# LJU_SNAP.net
KiCad netlist of a schematic drawn in Altium Designer
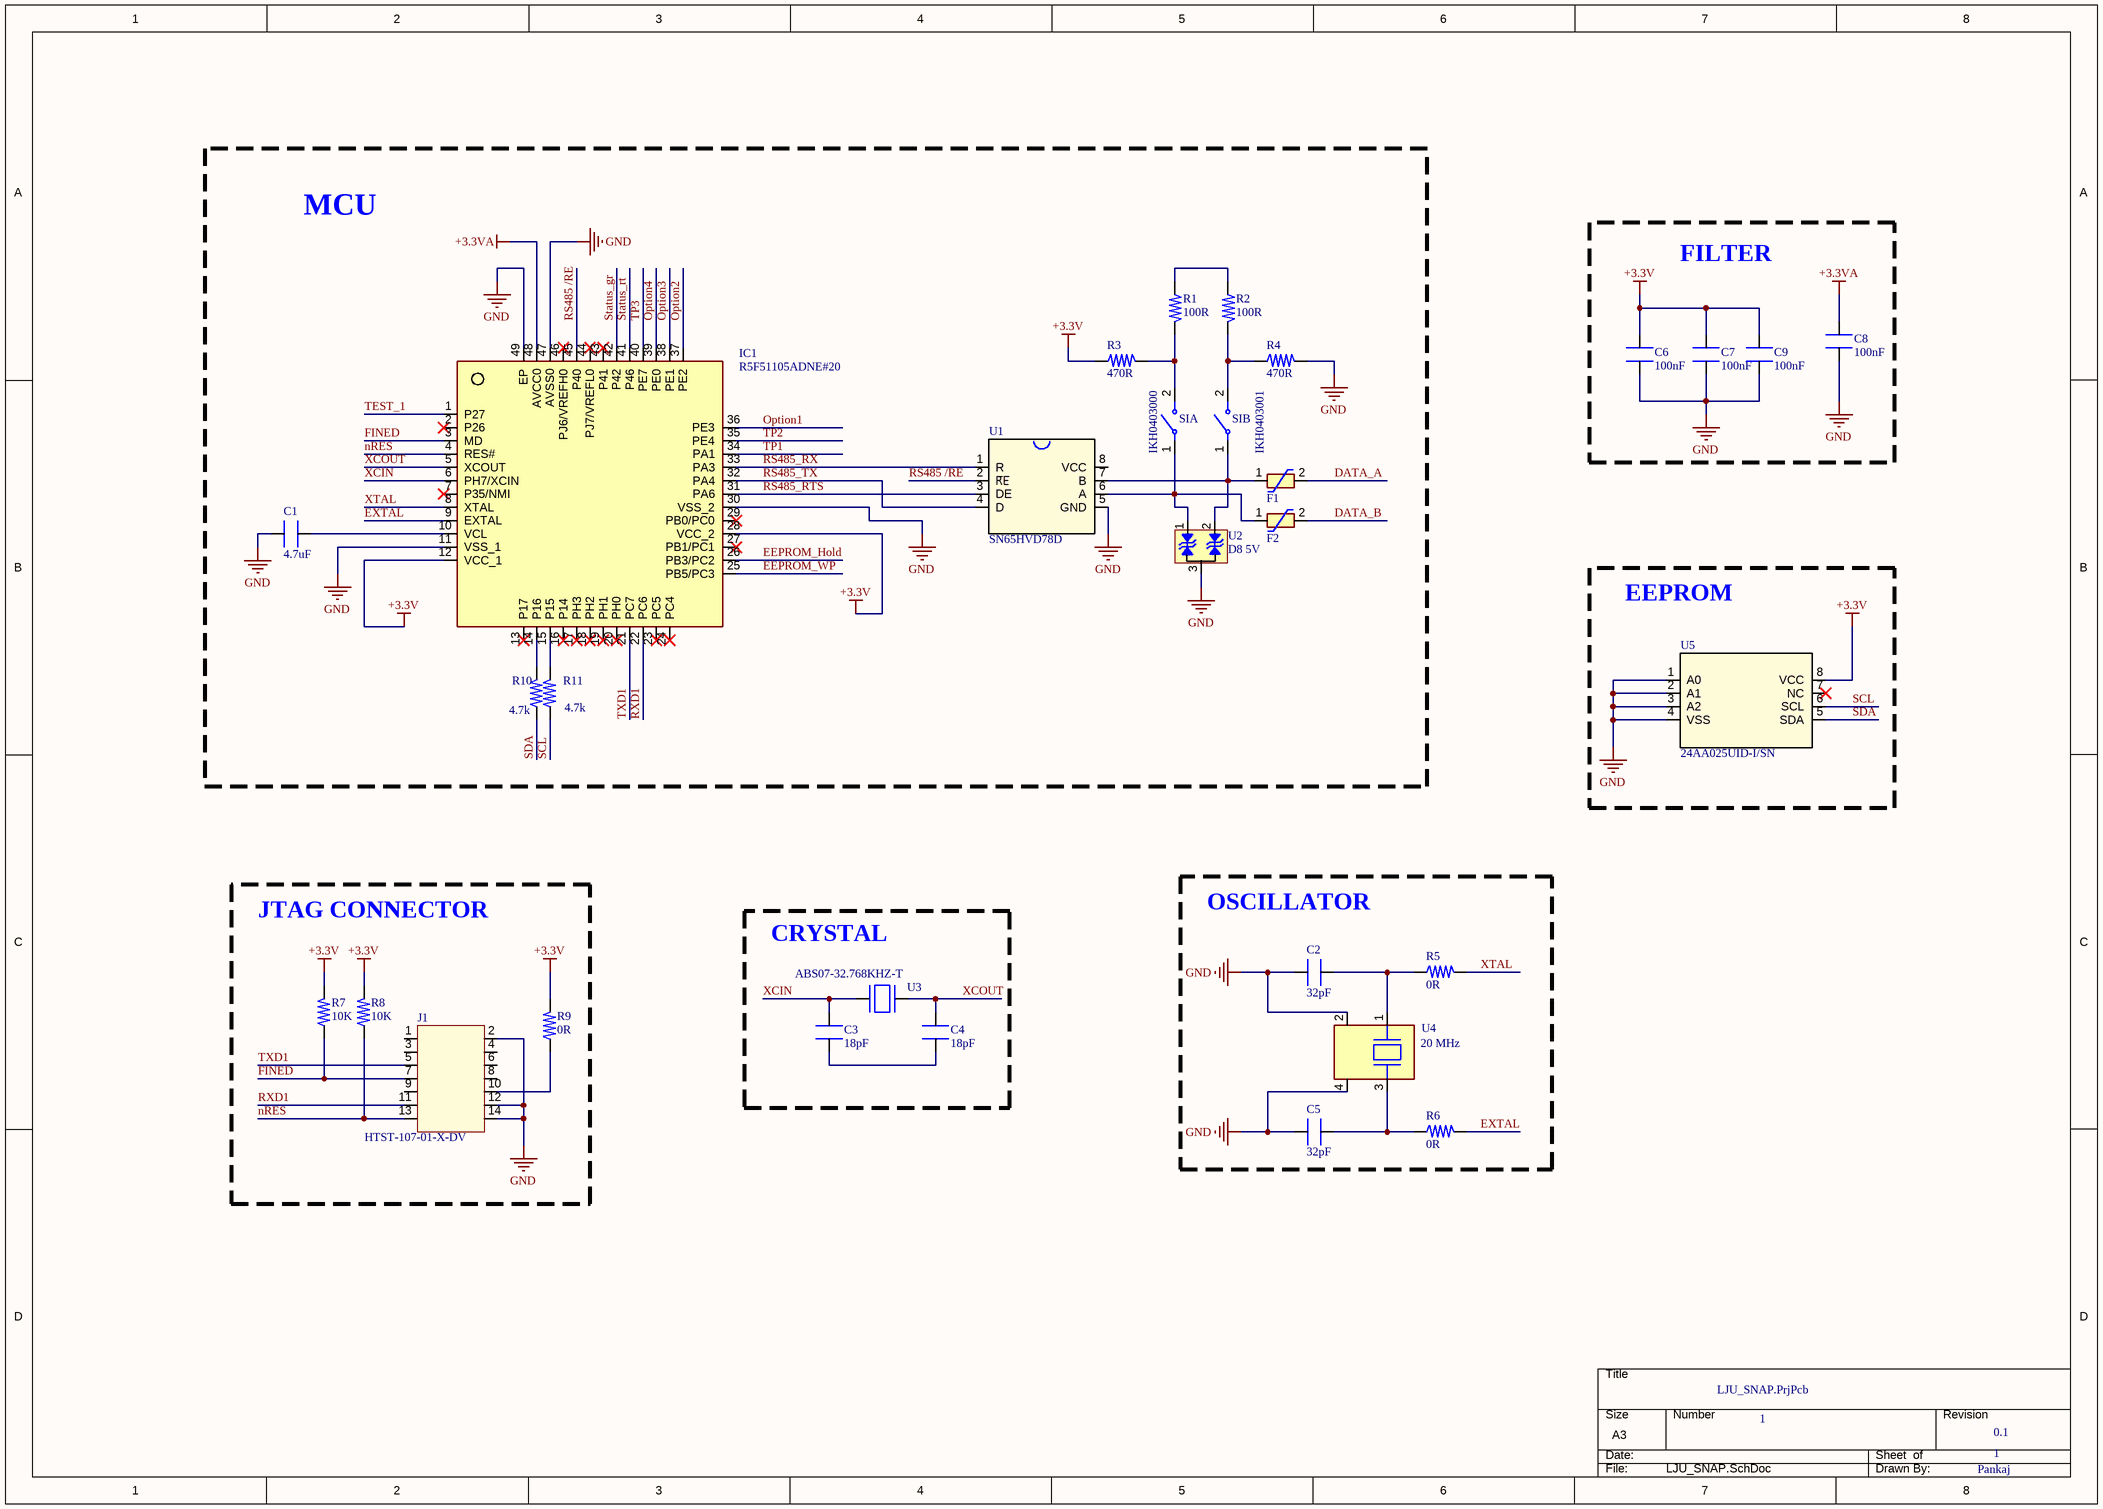
[diagram p0: LJU_SNAP.SchDoc]

(export (version "E")
  (design (tool "Eeschema 10.0.6"))
  (components
    (comp (ref "C1")
      (value "4.7uF")
      (footprint "CAP")
      (description "4.7 µF ±10% 25V Ceramic Capacitor X5R 0603 (1608 Metric)")
      (fields
        (field (name "MANUFACTURER") "KEMET")
        (field (name "MANUFACTURING PART NUMBER") "C0603C104K5RACTU")
      )
      (libsource (lib "SCH_LIB") (part "GRM188R61E475KE11D"))
    )
    (comp (ref "C2")
      (value "32pF")
      (footprint "CAP")
      (description "32 pF ±1% 50V Ceramic Capacitor C0G, NP0 0603 (1608 Metric)")
      (fields
        (field (name "MANUFACTURER") "KEMET")
        (field (name "MANUFACTURING PART NUMBER") "C0603C104K5RACTU")
      )
      (libsource (lib "SCH_LIB") (part "06035A320FAT4A"))
    )
    (comp (ref "C3")
      (value "18pF")
      (footprint "CAP")
      (description "CAP THIN FILM 21PF 25V 0402")
      (fields
        (field (name "MANUFACTURER") "KEMET")
        (field (name "MANUFACTURING PART NUMBER") "C0603C104K5RACTU")
      )
      (libsource (lib "SCH_LIB") (part "04023K210FBWTR{backslash}500"))
    )
    (comp (ref "C4")
      (value "18pF")
      (footprint "CAP")
      (description "CAP THIN FILM 21PF 25V 0402")
      (fields
        (field (name "MANUFACTURER") "KEMET")
        (field (name "MANUFACTURING PART NUMBER") "C0603C104K5RACTU")
      )
      (libsource (lib "SCH_LIB") (part "04023K210FBWTR{backslash}500"))
    )
    (comp (ref "C5")
      (value "32pF")
      (footprint "CAP")
      (description "32 pF ±1% 50V Ceramic Capacitor C0G, NP0 0603 (1608 Metric)")
      (fields
        (field (name "MANUFACTURER") "KEMET")
        (field (name "MANUFACTURING PART NUMBER") "C0603C104K5RACTU")
      )
      (libsource (lib "SCH_LIB") (part "06035A320FAT4A"))
    )
    (comp (ref "C6")
      (value "100nF")
      (footprint "CAP")
      (description "100 nF ±10% 100V Ceramic Capacitor X8L 0603 (1608 Metric)")
      (fields
        (field (name "MANUFACTURER") "KEMET")
        (field (name "MANUFACTURING PART NUMBER") "C0603C104K5RACTU")
      )
      (libsource (lib "SCH_LIB") (part "CL10E104KC8VPNC"))
    )
    (comp (ref "C7")
      (value "100nF")
      (footprint "CAP")
      (description "100 nF ±10% 100V Ceramic Capacitor X8L 0603 (1608 Metric)")
      (fields
        (field (name "MANUFACTURER") "KEMET")
        (field (name "MANUFACTURING PART NUMBER") "C0603C104K5RACTU")
      )
      (libsource (lib "SCH_LIB") (part "CL10E104KC8VPNC"))
    )
    (comp (ref "C8")
      (value "100nF")
      (footprint "CAP")
      (description "100 nF ±10% 100V Ceramic Capacitor X8L 0603 (1608 Metric)")
      (fields
        (field (name "MANUFACTURER") "KEMET")
        (field (name "MANUFACTURING PART NUMBER") "C0603C104K5RACTU")
      )
      (libsource (lib "SCH_LIB") (part "CL10E104KC8VPNC"))
    )
    (comp (ref "C9")
      (value "100nF")
      (footprint "CAP")
      (description "100 nF ±10% 100V Ceramic Capacitor X8L 0603 (1608 Metric)")
      (fields
        (field (name "MANUFACTURER") "KEMET")
        (field (name "MANUFACTURING PART NUMBER") "C0603C104K5RACTU")
      )
      (libsource (lib "SCH_LIB") (part "CL10E104KC8VPNC"))
    )
    (comp (ref "F1")
      (value "FUSE")
      (footprint "RESC3216X125N")
      (description "Polymeric PTC Resettable Fuse 24V 200 mA Ih Surface Mount 1206 (3216 Metric), Concave")
      (fields (field (name "MF") "Panasonic") (field (name "MP") "ERB-RE5R00V"))
      (libsource (lib "SCH_LIB") (part "PTS120624V020"))
    )
    (comp (ref "F2")
      (value "FUSE")
      (footprint "RESC3216X125N")
      (description "Polymeric PTC Resettable Fuse 24V 200 mA Ih Surface Mount 1206 (3216 Metric), Concave")
      (fields (field (name "MF") "Panasonic") (field (name "MP") "ERB-RE5R00V"))
      (libsource (lib "SCH_LIB") (part "PTS120624V020"))
    )
    (comp (ref "IC1")
      (value "R5F51105ADNE#20")
      (footprint "PCB_LIB:QFN50P700X700X80-49N-D")
      (description "Integrated Circuit")
      (libsource (lib "SCH_LIB") (part "R5F51105ADNE#20"))
    )
    (comp (ref "IKH1")
      (value "SIA")
      (footprint "SW_DS01-254-L-01BE")
      (libsource (lib "SCH_LIB") (part "IKH0403000"))
    )
    (comp (ref "IKH2")
      (value "SIB")
      (footprint "SW_DS01-254-L-01BE")
      (libsource (lib "SCH_LIB") (part "IKH0403000"))
    )
    (comp (ref "J1")
      (value "HTST-107-01-X-DV")
      (footprint "SAMTEC-HTST-107-01-X-DV")
      (fields (field (name "MP") "SAMTEC-HTST-107-01-X-DV"))
      (libsource (lib "SCH_LIB") (part "SAMTEC-HTST-107-01-X-DV"))
    )
    (comp (ref "R1")
      (value "100R")
      (footprint "RES")
      (description "100 Ohms ±1% 0.1W, 1/10W Chip Resistor 0603 (1608 Metric) Moisture Resistant Thick Film")
      (fields
        (field (name "MANUFACTURER") "Vishay Dale")
        (field (name "MANUFACTURER PART NUMBER") "CRCW0603590KFKEA")
      )
      (libsource (lib "SCH_LIB") (part "RC0603FR-07100RL"))
    )
    (comp (ref "R2")
      (value "100R")
      (footprint "RES")
      (description "100 Ohms ±1% 0.1W, 1/10W Chip Resistor 0603 (1608 Metric) Moisture Resistant Thick Film")
      (fields
        (field (name "MANUFACTURER") "Vishay Dale")
        (field (name "MANUFACTURER PART NUMBER") "CRCW0603590KFKEA")
      )
      (libsource (lib "SCH_LIB") (part "RC0603FR-07100RL"))
    )
    (comp (ref "R3")
      (value "470R")
      (footprint "RES")
      (description "470 Ohms ±5% 0.1W, 1/10W Chip Resistor 0603 (1608 Metric) Moisture Resistant Thick Film")
      (fields
        (field (name "MANUFACTURER") "Vishay Dale")
        (field (name "MANUFACTURER PART NUMBER") "CRCW0603590KFKEA")
      )
      (libsource (lib "SCH_LIB") (part "RC0603JR-07470RL"))
    )
    (comp (ref "R4")
      (value "470R")
      (footprint "RES")
      (description "470 Ohms ±5% 0.1W, 1/10W Chip Resistor 0603 (1608 Metric) Moisture Resistant Thick Film")
      (fields
        (field (name "MANUFACTURER") "Vishay Dale")
        (field (name "MANUFACTURER PART NUMBER") "CRCW0603590KFKEA")
      )
      (libsource (lib "SCH_LIB") (part "RC0603JR-07470RL"))
    )
    (comp (ref "R5")
      (value "0R")
      (footprint "RES")
      (description "0 Ohms Jumper 0.1W, 1/10W Chip Resistor 0603 (1608 Metric) Thick Film")
      (fields
        (field (name "MANUFACTURER") "YAGEO")
        (field (name "MANUFACTURER PART NUMBER") "RC0603FR-0710KL")
      )
      (libsource (lib "SCH_LIB") (part "CR0603PB0RS001"))
    )
    (comp (ref "R6")
      (value "0R")
      (footprint "RES")
      (description "0 Ohms Jumper 0.1W, 1/10W Chip Resistor 0603 (1608 Metric) Thick Film")
      (fields
        (field (name "MANUFACTURER") "YAGEO")
        (field (name "MANUFACTURER PART NUMBER") "RC0603FR-0710KL")
      )
      (libsource (lib "SCH_LIB") (part "CR0603PB0RS001"))
    )
    (comp (ref "R7")
      (value "10K")
      (footprint "RES")
      (description "10 kOhms ±1% 0.1W, 1/10W Chip Resistor 0603 (1608 Metric) Moisture Resistant Thick Film")
      (fields
        (field (name "MANUFACTURER") "YAGEO")
        (field (name "MANUFACTURER PART NUMBER") "RC0603FR-0710KL")
      )
      (libsource (lib "SCH_LIB") (part "RC0603FR-0710KL"))
    )
    (comp (ref "R8")
      (value "10K")
      (footprint "RES")
      (description "10 kOhms ±1% 0.1W, 1/10W Chip Resistor 0603 (1608 Metric) Moisture Resistant Thick Film")
      (fields
        (field (name "MANUFACTURER") "YAGEO")
        (field (name "MANUFACTURER PART NUMBER") "RC0603FR-0710KL")
      )
      (libsource (lib "SCH_LIB") (part "RC0603FR-0710KL"))
    )
    (comp (ref "R9")
      (value "0R")
      (footprint "RES")
      (description "0 Ohms Jumper 0.1W, 1/10W Chip Resistor 0603 (1608 Metric) Thick Film")
      (fields
        (field (name "MANUFACTURER") "YAGEO")
        (field (name "MANUFACTURER PART NUMBER") "RC0603FR-0710KL")
      )
      (libsource (lib "SCH_LIB") (part "CR0603PB0RS001"))
    )
    (comp (ref "R10")
      (value "4.7k")
      (footprint "RES")
      (description "4.7 kOhms ±1% 0.1W, 1/10W Chip Resistor 0603 (1608 Metric) Moisture Resistant Thick Film")
      (fields
        (field (name "MANUFACTURER") "YAGEO")
        (field (name "MANUFACTURER PART NUMBER") "RC0603FR-0710KL")
      )
      (libsource (lib "SCH_LIB") (part "RC0603FR-074K7L"))
    )
    (comp (ref "R11")
      (value "4.7k")
      (footprint "RES")
      (description "4.7 kOhms ±1% 0.1W, 1/10W Chip Resistor 0603 (1608 Metric) Moisture Resistant Thick Film")
      (fields
        (field (name "MANUFACTURER") "YAGEO")
        (field (name "MANUFACTURER PART NUMBER") "RC0603FR-0710KL")
      )
      (libsource (lib "SCH_LIB") (part "RC0603FR-074K7L"))
    )
    (comp (ref "U1")
      (value "SN65HVD78D")
      (footprint "D8_TEX")
      (description "3.3 V Half-Duplex RS-485, with IEC ESD, 50 Mbps 8-SOIC -40 to 125")
      (fields (field (name "COPYRIGHT") "Copyright (C) 2025 Ultra Librarian. All rights reserved."))
      (libsource (lib "SCH_LIB") (part "SN65HVD78D"))
    )
    (comp (ref "U2")
      (value "D8 5V")
      (footprint "SOT-23-3_DBZ_TEX")
      (description "Two-channel bidirectional 12V ESD protection diode 3-SOT-23 -40 to 125")
      (libsource (lib "SCH_LIB") (part "ESD562DBZR"))
    )
    (comp (ref "U3")
      (value "ABS07-32.768KHZ-T")
      (footprint "XTAL_ABS07-32.768KHZ-T")
      (description "32.768 kHz Â±20ppm Crystal 12.5pF 70 kOhms 2-SMD, No Lead")
      (fields (field (name "MF") "Abracon"))
      (libsource (lib "SCH_LIB") (part "ABS07-32.768KHZ-T"))
    )
    (comp (ref "U4")
      (value "20 MHz")
      (footprint "XTAL_ABM8AIG-20.000MHZ-12-2Z-T3")
      (description "20 MHz Â±20ppm Crystal 12pF 50 Ohms 4-SMD, No Lead")
      (fields (field (name "MP") "ABM8AIG-20.000MHZ-12-2Z-T3") (field (name "MF") "Abracon"))
      (libsource (lib "SCH_LIB") (part "ABM8AIG-20.000MHZ-12-2Z-T3"))
    )
    (comp (ref "U5")
      (value "24AA025UID-I/SN")
      (footprint "SOIC8-N_MC_MCH")
      (description "EEPROM Memory IC 2Kbit I2C 400 kHz 900 ns 8-SOIC")
      (fields (field (name "COPYRIGHT") "Copyright (C) 2025 Ultra Librarian. All rights reserved."))
      (libsource (lib "SCH_LIB") (part "24AA025UID-ISN"))
    )
  )
  (nets
    (net (code "1") (name "+3.3V") (class "Default")
      (node (ref "C6") (pin "2") (pinfunction "2_2") (pintype "passive"))
      (node (ref "C7") (pin "2") (pinfunction "2_2") (pintype "passive"))
      (node (ref "C9") (pin "2") (pinfunction "2_2") (pintype "passive"))
      (node (ref "IC1") (pin "12") (pinfunction "VCC_1_12") (pintype "passive"))
      (node (ref "IC1") (pin "28") (pinfunction "VCC_2_28") (pintype "passive"))
      (node (ref "R3") (pin "1") (pinfunction "1_1") (pintype "passive"))
      (node (ref "R7") (pin "2") (pinfunction "2_2") (pintype "passive"))
      (node (ref "R8") (pin "2") (pinfunction "2_2") (pintype "passive"))
      (node (ref "R9") (pin "2") (pinfunction "2_2") (pintype "passive"))
      (node (ref "U5") (pin "8") (pinfunction "VCC_8") (pintype "passive"))
    )
    (net (code "2") (name "+3.3VA") (class "Default")
      (node (ref "C8") (pin "2") (pinfunction "2_2") (pintype "passive"))
      (node (ref "IC1") (pin "48") (pinfunction "AVCC0_48") (pintype "passive"))
    )
    (net (code "3") (name "/DATA_A") (class "Default")
      (node (ref "F1") (pin "2") (pinfunction "2_2") (pintype "passive"))
    )
    (net (code "4") (name "/DATA_B") (class "Default")
      (node (ref "F2") (pin "2") (pinfunction "2_2") (pintype "passive"))
    )
    (net (code "5") (name "/EEPROM_Hold") (class "Default")
      (node (ref "IC1") (pin "26") (pinfunction "PB3/PC2_26") (pintype "passive"))
    )
    (net (code "6") (name "/EEPROM_WP") (class "Default")
      (node (ref "IC1") (pin "25") (pinfunction "PB5/PC3_25") (pintype "passive"))
    )
    (net (code "7") (name "/EXTAL") (class "Default")
      (node (ref "IC1") (pin "9") (pinfunction "EXTAL_9") (pintype "passive"))
      (node (ref "R6") (pin "2") (pinfunction "2_2") (pintype "passive"))
    )
    (net (code "8") (name "/FINED") (class "Default")
      (node (ref "IC1") (pin "3") (pinfunction "MD_3") (pintype "passive"))
      (node (ref "J1") (pin "7") (pinfunction "7_7") (pintype "passive"))
      (node (ref "R7") (pin "1") (pinfunction "1_1") (pintype "passive"))
    )
    (net (code "9") (name "/Option1") (class "Default")
      (node (ref "IC1") (pin "36") (pinfunction "PE3_36") (pintype "passive"))
    )
    (net (code "10") (name "/Option2") (class "Default")
      (node (ref "IC1") (pin "37") (pinfunction "PE2_37") (pintype "passive"))
    )
    (net (code "11") (name "/Option3") (class "Default")
      (node (ref "IC1") (pin "38") (pinfunction "PE1_38") (pintype "passive"))
    )
    (net (code "12") (name "/Option4") (class "Default")
      (node (ref "IC1") (pin "39") (pinfunction "PE0_39") (pintype "passive"))
    )
    (net (code "13") (name "/RS485 {slash}RE") (class "Default")
      (node (ref "IC1") (pin "45") (pinfunction "P40_45") (pintype "passive"))
      (node (ref "U1") (pin "2") (pinfunction "R̅E̅_2") (pintype "passive"))
    )
    (net (code "14") (name "/RS485_RTS") (class "Default")
      (node (ref "IC1") (pin "31") (pinfunction "PA6_31") (pintype "passive"))
      (node (ref "U1") (pin "3") (pinfunction "DE_3") (pintype "passive"))
    )
    (net (code "15") (name "/RS485_RX") (class "Default")
      (node (ref "IC1") (pin "33") (pinfunction "PA3_33") (pintype "passive"))
      (node (ref "U1") (pin "1") (pinfunction "R_1") (pintype "passive"))
    )
    (net (code "16") (name "/RS485_TX") (class "Default")
      (node (ref "IC1") (pin "32") (pinfunction "PA4_32") (pintype "passive"))
      (node (ref "U1") (pin "4") (pinfunction "D_4") (pintype "passive"))
    )
    (net (code "17") (name "/RXD1") (class "Default")
      (node (ref "IC1") (pin "22") (pinfunction "PC6_22") (pintype "passive"))
      (node (ref "J1") (pin "11") (pinfunction "11_11") (pintype "passive"))
    )
    (net (code "18") (name "/SCL") (class "Default")
      (node (ref "R11") (pin "1") (pinfunction "1_1") (pintype "passive"))
      (node (ref "U5") (pin "6") (pinfunction "SCL_6") (pintype "passive"))
    )
    (net (code "19") (name "/SDA") (class "Default")
      (node (ref "R10") (pin "1") (pinfunction "1_1") (pintype "passive"))
      (node (ref "U5") (pin "5") (pinfunction "SDA_5") (pintype "passive"))
    )
    (net (code "20") (name "/Status_gr") (class "Default")
      (node (ref "IC1") (pin "42") (pinfunction "P42_42") (pintype "passive"))
    )
    (net (code "21") (name "/Status_rt") (class "Default")
      (node (ref "IC1") (pin "41") (pinfunction "P46_41") (pintype "passive"))
    )
    (net (code "22") (name "/TEST_1") (class "Default")
      (node (ref "IC1") (pin "1") (pinfunction "P27_1") (pintype "passive"))
    )
    (net (code "23") (name "/TP1") (class "Default")
      (node (ref "IC1") (pin "34") (pinfunction "PA1_34") (pintype "passive"))
    )
    (net (code "24") (name "/TP2") (class "Default")
      (node (ref "IC1") (pin "35") (pinfunction "PE4_35") (pintype "passive"))
    )
    (net (code "25") (name "/TP3") (class "Default")
      (node (ref "IC1") (pin "40") (pinfunction "PE7_40") (pintype "passive"))
    )
    (net (code "26") (name "/TXD1") (class "Default")
      (node (ref "IC1") (pin "21") (pinfunction "PC7_21") (pintype "passive"))
      (node (ref "J1") (pin "5") (pinfunction "5_5") (pintype "passive"))
    )
    (net (code "27") (name "/XCIN") (class "Default")
      (node (ref "C3") (pin "2") (pinfunction "2_2") (pintype "passive"))
      (node (ref "IC1") (pin "6") (pinfunction "PH7/XCIN_6") (pintype "passive"))
      (node (ref "U3") (pin "1") (pinfunction "1_1") (pintype "passive"))
    )
    (net (code "28") (name "/XCOUT") (class "Default")
      (node (ref "C4") (pin "2") (pinfunction "2_2") (pintype "passive"))
      (node (ref "IC1") (pin "5") (pinfunction "XCOUT_5") (pintype "passive"))
      (node (ref "U3") (pin "2") (pinfunction "2_2") (pintype "passive"))
    )
    (net (code "29") (name "/XTAL") (class "Default")
      (node (ref "IC1") (pin "8") (pinfunction "XTAL_8") (pintype "passive"))
      (node (ref "R5") (pin "2") (pinfunction "2_2") (pintype "passive"))
    )
    (net (code "30") (name "/nRES") (class "Default")
      (node (ref "IC1") (pin "4") (pinfunction "RES#_4") (pintype "passive"))
      (node (ref "J1") (pin "13") (pinfunction "13_13") (pintype "passive"))
      (node (ref "R8") (pin "1") (pinfunction "1_1") (pintype "passive"))
    )
    (net (code "31") (name "GND") (class "Default")
      (node (ref "C1") (pin "1") (pinfunction "1_1") (pintype "passive"))
      (node (ref "C2") (pin "1") (pinfunction "1_1") (pintype "passive"))
      (node (ref "C5") (pin "1") (pinfunction "1_1") (pintype "passive"))
      (node (ref "C6") (pin "1") (pinfunction "1_1") (pintype "passive"))
      (node (ref "C7") (pin "1") (pinfunction "1_1") (pintype "passive"))
      (node (ref "C8") (pin "1") (pinfunction "1_1") (pintype "passive"))
      (node (ref "C9") (pin "1") (pinfunction "1_1") (pintype "passive"))
      (node (ref "IC1") (pin "11") (pinfunction "VSS_1_11") (pintype "passive"))
      (node (ref "IC1") (pin "30") (pinfunction "VSS_2_30") (pintype "passive"))
      (node (ref "IC1") (pin "47") (pinfunction "AVSS0_47") (pintype "passive"))
      (node (ref "IC1") (pin "49") (pinfunction "EP_49") (pintype "passive"))
      (node (ref "J1") (pin "12") (pinfunction "12_12") (pintype "passive"))
      (node (ref "J1") (pin "14") (pinfunction "14_14") (pintype "passive"))
      (node (ref "J1") (pin "2") (pinfunction "2_2") (pintype "passive"))
      (node (ref "R4") (pin "2") (pinfunction "2_2") (pintype "passive"))
      (node (ref "U1") (pin "5") (pinfunction "GND_5") (pintype "power_in"))
      (node (ref "U2") (pin "3") (pinfunction "3_3") (pintype "passive"))
      (node (ref "U4") (pin "2") (pinfunction "GND_2") (pintype "power_in"))
      (node (ref "U4") (pin "4") (pinfunction "GND_4") (pintype "power_in"))
      (node (ref "U5") (pin "1") (pinfunction "A0_1") (pintype "passive"))
      (node (ref "U5") (pin "2") (pinfunction "A1_2") (pintype "passive"))
      (node (ref "U5") (pin "3") (pinfunction "A2_3") (pintype "passive"))
      (node (ref "U5") (pin "4") (pinfunction "VSS_4") (pintype "passive"))
    )
    (net (code "32") (name "Net-(C2-Pad2)") (class "Default")
      (node (ref "C2") (pin "2") (pinfunction "2_2") (pintype "passive"))
      (node (ref "R5") (pin "1") (pinfunction "1_1") (pintype "passive"))
      (node (ref "U4") (pin "1") (pinfunction "1_1") (pintype "passive"))
    )
    (net (code "33") (name "Net-(C3-Pad1)") (class "Default")
      (node (ref "C3") (pin "1") (pinfunction "1_1") (pintype "passive"))
      (node (ref "C4") (pin "1") (pinfunction "1_1") (pintype "passive"))
    )
    (net (code "34") (name "Net-(IC1-P15)") (class "Default")
      (node (ref "IC1") (pin "15") (pinfunction "P15_15") (pintype "passive"))
      (node (ref "R11") (pin "2") (pinfunction "2_2") (pintype "passive"))
    )
    (net (code "35") (name "Net-(IC1-P16)") (class "Default")
      (node (ref "IC1") (pin "14") (pinfunction "P16_14") (pintype "passive"))
      (node (ref "R10") (pin "2") (pinfunction "2_2") (pintype "passive"))
    )
    (net (code "36") (name "Net-(IC1-VCL)") (class "Default")
      (node (ref "C1") (pin "2") (pinfunction "2_2") (pintype "passive"))
      (node (ref "IC1") (pin "10") (pinfunction "VCL_10") (pintype "passive"))
    )
    (net (code "37") (name "Net-(IKH1-Pad2)") (class "Default")
      (node (ref "IKH1") (pin "2") (pinfunction "2_2") (pintype "passive"))
      (node (ref "R1") (pin "2") (pinfunction "2_2") (pintype "passive"))
      (node (ref "R3") (pin "2") (pinfunction "2_2") (pintype "passive"))
    )
    (net (code "38") (name "Net-(IKH2-Pad2)") (class "Default")
      (node (ref "IKH2") (pin "2") (pinfunction "2_2") (pintype "passive"))
      (node (ref "R2") (pin "2") (pinfunction "2_2") (pintype "passive"))
      (node (ref "R4") (pin "1") (pinfunction "1_1") (pintype "passive"))
    )
    (net (code "39") (name "Net-(J1-Pad10)") (class "Default")
      (node (ref "J1") (pin "10") (pinfunction "10_10") (pintype "passive"))
      (node (ref "R9") (pin "1") (pinfunction "1_1") (pintype "passive"))
    )
    (net (code "40") (name "Net-(R1-Pad1)") (class "Default")
      (node (ref "R1") (pin "1") (pinfunction "1_1") (pintype "passive"))
      (node (ref "R2") (pin "1") (pinfunction "1_1") (pintype "passive"))
    )
    (net (code "41") (name "Net-(U1-A)") (class "Default")
      (node (ref "F2") (pin "1") (pinfunction "1_1") (pintype "passive"))
      (node (ref "IKH1") (pin "1") (pinfunction "1_1") (pintype "passive"))
      (node (ref "U1") (pin "6") (pinfunction "A_6") (pintype "passive"))
      (node (ref "U2") (pin "1") (pintype "passive"))
    )
    (net (code "42") (name "Net-(U1-B)") (class "Default")
      (node (ref "F1") (pin "1") (pinfunction "1_1") (pintype "passive"))
      (node (ref "IKH2") (pin "1") (pinfunction "1_1") (pintype "passive"))
      (node (ref "U1") (pin "7") (pinfunction "B_7") (pintype "passive"))
      (node (ref "U2") (pin "2") (pintype "passive"))
    )
    (net (code "43") (name "Net-(U4-2)") (class "Default")
      (node (ref "C5") (pin "2") (pinfunction "2_2") (pintype "passive"))
      (node (ref "R6") (pin "1") (pinfunction "1_1") (pintype "passive"))
      (node (ref "U4") (pin "3") (pinfunction "2_3") (pintype "passive"))
    )
    (net (code "44") (name "unconnected-(IC1-P14-Pad16)") (class "Default")
      (node (ref "IC1") (pin "16") (pinfunction "P14_16") (pintype "passive+no_connect"))
    )
    (net (code "45") (name "unconnected-(IC1-P17-Pad13)") (class "Default")
      (node (ref "IC1") (pin "13") (pinfunction "P17_13") (pintype "passive+no_connect"))
    )
    (net (code "46") (name "unconnected-(IC1-P26-Pad2)") (class "Default")
      (node (ref "IC1") (pin "2") (pinfunction "P26_2") (pintype "passive+no_connect"))
    )
    (net (code "47") (name "unconnected-(IC1-P35{slash}NMI-Pad7)") (class "Default")
      (node (ref "IC1") (pin "7") (pinfunction "P35/NMI_7") (pintype "passive+no_connect"))
    )
    (net (code "48") (name "unconnected-(IC1-P41-Pad43)") (class "Default")
      (node (ref "IC1") (pin "43") (pinfunction "P41_43") (pintype "passive+no_connect"))
    )
    (net (code "49") (name "unconnected-(IC1-PB0{slash}PC0-Pad29)") (class "Default")
      (node (ref "IC1") (pin "29") (pinfunction "PB0/PC0_29") (pintype "passive+no_connect"))
    )
    (net (code "50") (name "unconnected-(IC1-PB1{slash}PC1-Pad27)") (class "Default")
      (node (ref "IC1") (pin "27") (pinfunction "PB1/PC1_27") (pintype "passive+no_connect"))
    )
    (net (code "51") (name "unconnected-(IC1-PC4-Pad24)") (class "Default")
      (node (ref "IC1") (pin "24") (pinfunction "PC4_24") (pintype "passive+no_connect"))
    )
    (net (code "52") (name "unconnected-(IC1-PC5-Pad23)") (class "Default")
      (node (ref "IC1") (pin "23") (pinfunction "PC5_23") (pintype "passive+no_connect"))
    )
    (net (code "53") (name "unconnected-(IC1-PH0-Pad20)") (class "Default")
      (node (ref "IC1") (pin "20") (pinfunction "PH0_20") (pintype "passive+no_connect"))
    )
    (net (code "54") (name "unconnected-(IC1-PH1-Pad19)") (class "Default")
      (node (ref "IC1") (pin "19") (pinfunction "PH1_19") (pintype "passive+no_connect"))
    )
    (net (code "55") (name "unconnected-(IC1-PH2-Pad18)") (class "Default")
      (node (ref "IC1") (pin "18") (pinfunction "PH2_18") (pintype "passive+no_connect"))
    )
    (net (code "56") (name "unconnected-(IC1-PH3-Pad17)") (class "Default")
      (node (ref "IC1") (pin "17") (pinfunction "PH3_17") (pintype "passive+no_connect"))
    )
    (net (code "57") (name "unconnected-(IC1-PJ6{slash}VREFH0-Pad46)") (class "Default")
      (node (ref "IC1") (pin "46") (pinfunction "PJ6/VREFH0_46") (pintype "passive+no_connect"))
    )
    (net (code "58") (name "unconnected-(IC1-PJ7{slash}VREFL0-Pad44)") (class "Default")
      (node (ref "IC1") (pin "44") (pinfunction "PJ7/VREFL0_44") (pintype "passive+no_connect"))
    )
    (net (code "59") (name "unconnected-(J1-Pad1)") (class "Default")
      (node (ref "J1") (pin "1") (pinfunction "1_1") (pintype "passive"))
    )
    (net (code "60") (name "unconnected-(J1-Pad3)") (class "Default")
      (node (ref "J1") (pin "3") (pinfunction "3_3") (pintype "passive"))
    )
    (net (code "61") (name "unconnected-(J1-Pad4)") (class "Default")
      (node (ref "J1") (pin "4") (pinfunction "4_4") (pintype "passive"))
    )
    (net (code "62") (name "unconnected-(J1-Pad6)") (class "Default")
      (node (ref "J1") (pin "6") (pinfunction "6_6") (pintype "passive"))
    )
    (net (code "63") (name "unconnected-(J1-Pad8)") (class "Default")
      (node (ref "J1") (pin "8") (pinfunction "8_8") (pintype "passive"))
    )
    (net (code "64") (name "unconnected-(J1-Pad9)") (class "Default")
      (node (ref "J1") (pin "9") (pinfunction "9_9") (pintype "passive"))
    )
    (net (code "65") (name "unconnected-(U1-VCC-Pad8)") (class "Default")
      (node (ref "U1") (pin "8") (pinfunction "VCC_8") (pintype "power_in"))
    )
    (net (code "66") (name "unconnected-(U5-NC-Pad7)") (class "Default")
      (node (ref "U5") (pin "7") (pinfunction "NC_7") (pintype "passive+no_connect"))
    )
  )
)
